# Connectors.net
KiCad netlist of a schematic drawn in Altium Designer
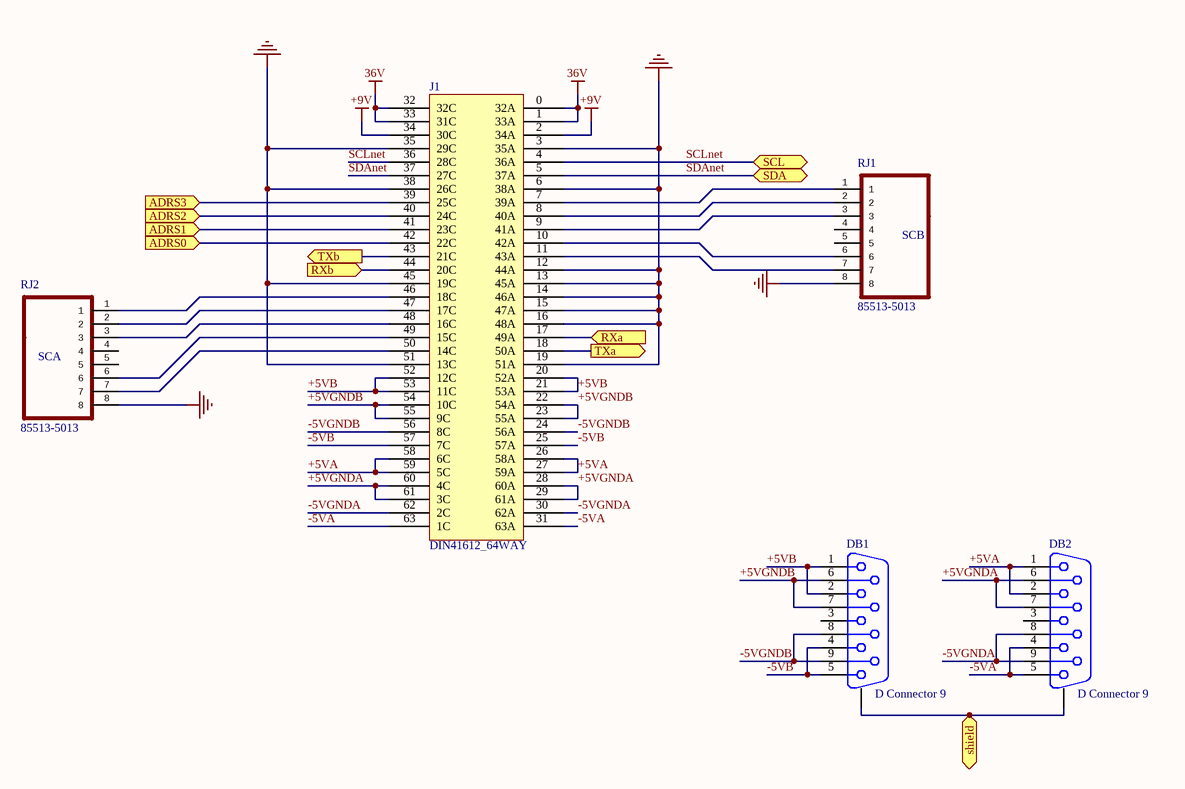
[diagram p0: Connectors.SchDoc]

(export (version "E")
  (design (tool "Eeschema 10.0.6"))
  (components
    (comp (ref "DB1")
      (value "D Connector 9")
      (footprint "DSUB1.STRAIGHT")
      (description "Receptacle Assembly, 9 Position, Right Angle")
      (fields (field (name "PARTNO") "L177TSEH09SOL2RM8") (field (name "PUBLISHER") "Altium Limited"))
      (libsource (lib "BACKPLANElib") (part "D Connector 9"))
    )
    (comp (ref "DB2")
      (value "D Connector 9")
      (footprint "DSUB1.STRAIGHT")
      (description "Receptacle Assembly, 9 Position, Right Angle")
      (fields (field (name "PARTNO") "L177TSEH09SOL2RM8") (field (name "PUBLISHER") "Altium Limited"))
      (libsource (lib "BACKPLANElib") (part "D Connector 9"))
    )
    (comp (ref "J1")
      (value "DIN41612_64WAY")
      (footprint "09 03 164 6919")
      (fields (field (name "PARTNO") "9-1393640-3"))
      (libsource (lib "BACKPLANElib") (part "DIN41612_64WAY"))
    )
    (comp (ref "RJ1")
      (value "85513-5013")
      (footprint "RJ45_SMD_VERT")
      (libsource (lib "BACKPLANElib") (part "85513-5013"))
    )
    (comp (ref "RJ2")
      (value "85513-5013")
      (footprint "RJ45_SMD_VERT")
      (libsource (lib "BACKPLANElib") (part "85513-5013"))
    )
  )
  (nets
    (net (code "1") (name "+9V") (class "Default")
      (node (ref "J1") (pin "2") (pinfunction "34A_2") (pintype "passive"))
      (node (ref "J1") (pin "34") (pinfunction "30C_34") (pintype "passive"))
    )
    (net (code "2") (name "/+5VA") (class "Default")
      (node (ref "DB2") (pin "1") (pinfunction "1_1") (pintype "passive"))
      (node (ref "DB2") (pin "2") (pinfunction "2_2") (pintype "passive"))
      (node (ref "J1") (pin "26") (pinfunction "58A_26") (pintype "passive"))
      (node (ref "J1") (pin "27") (pinfunction "59A_27") (pintype "passive"))
      (node (ref "J1") (pin "58") (pinfunction "6C_58") (pintype "passive"))
      (node (ref "J1") (pin "59") (pinfunction "5C_59") (pintype "passive"))
    )
    (net (code "3") (name "/+5VB") (class "Default")
      (node (ref "DB1") (pin "1") (pinfunction "1_1") (pintype "passive"))
      (node (ref "DB1") (pin "2") (pinfunction "2_2") (pintype "passive"))
      (node (ref "J1") (pin "20") (pinfunction "52A_20") (pintype "passive"))
      (node (ref "J1") (pin "21") (pinfunction "53A_21") (pintype "passive"))
      (node (ref "J1") (pin "52") (pinfunction "12C_52") (pintype "passive"))
      (node (ref "J1") (pin "53") (pinfunction "11C_53") (pintype "passive"))
    )
    (net (code "4") (name "/+5VGNDA") (class "Default")
      (node (ref "DB2") (pin "6") (pinfunction "6_6") (pintype "passive"))
      (node (ref "DB2") (pin "7") (pinfunction "7_7") (pintype "passive"))
      (node (ref "J1") (pin "28") (pinfunction "60A_28") (pintype "passive"))
      (node (ref "J1") (pin "29") (pinfunction "61A_29") (pintype "passive"))
      (node (ref "J1") (pin "60") (pinfunction "4C_60") (pintype "passive"))
      (node (ref "J1") (pin "61") (pinfunction "3C_61") (pintype "passive"))
    )
    (net (code "5") (name "/+5VGNDB") (class "Default")
      (node (ref "DB1") (pin "6") (pinfunction "6_6") (pintype "passive"))
      (node (ref "DB1") (pin "7") (pinfunction "7_7") (pintype "passive"))
      (node (ref "J1") (pin "22") (pinfunction "54A_22") (pintype "passive"))
      (node (ref "J1") (pin "23") (pinfunction "55A_23") (pintype "passive"))
      (node (ref "J1") (pin "54") (pinfunction "10C_54") (pintype "passive"))
      (node (ref "J1") (pin "55") (pinfunction "9C_55") (pintype "passive"))
    )
    (net (code "6") (name "/-5VA") (class "Default")
      (node (ref "DB2") (pin "4") (pinfunction "4_4") (pintype "passive"))
      (node (ref "DB2") (pin "5") (pinfunction "5_5") (pintype "passive"))
      (node (ref "J1") (pin "31") (pinfunction "63A_31") (pintype "passive"))
      (node (ref "J1") (pin "63") (pinfunction "1C_63") (pintype "passive"))
    )
    (net (code "7") (name "/-5VB") (class "Default")
      (node (ref "DB1") (pin "4") (pinfunction "4_4") (pintype "passive"))
      (node (ref "DB1") (pin "5") (pinfunction "5_5") (pintype "passive"))
      (node (ref "J1") (pin "25") (pinfunction "57A_25") (pintype "passive"))
      (node (ref "J1") (pin "57") (pinfunction "7C_57") (pintype "passive"))
    )
    (net (code "8") (name "/-5VGNDA") (class "Default")
      (node (ref "DB2") (pin "8") (pinfunction "8_8") (pintype "passive"))
      (node (ref "DB2") (pin "9") (pinfunction "9_9") (pintype "passive"))
      (node (ref "J1") (pin "30") (pinfunction "62A_30") (pintype "passive"))
      (node (ref "J1") (pin "62") (pinfunction "2C_62") (pintype "passive"))
    )
    (net (code "9") (name "/-5VGNDB") (class "Default")
      (node (ref "DB1") (pin "8") (pinfunction "8_8") (pintype "passive"))
      (node (ref "DB1") (pin "9") (pinfunction "9_9") (pintype "passive"))
      (node (ref "J1") (pin "24") (pinfunction "56A_24") (pintype "passive"))
      (node (ref "J1") (pin "56") (pinfunction "8C_56") (pintype "passive"))
    )
    (net (code "10") (name "/ADRS0") (class "Default")
      (node (ref "J1") (pin "42") (pinfunction "22C_42") (pintype "passive"))
    )
    (net (code "11") (name "/ADRS1") (class "Default")
      (node (ref "J1") (pin "41") (pinfunction "23C_41") (pintype "passive"))
    )
    (net (code "12") (name "/ADRS2") (class "Default")
      (node (ref "J1") (pin "40") (pinfunction "24C_40") (pintype "passive"))
    )
    (net (code "13") (name "/ADRS3") (class "Default")
      (node (ref "J1") (pin "39") (pinfunction "25C_39") (pintype "passive"))
    )
    (net (code "14") (name "/RXa") (class "Default")
      (node (ref "J1") (pin "17") (pinfunction "49A_17") (pintype "passive"))
    )
    (net (code "15") (name "/RXb") (class "Default")
      (node (ref "J1") (pin "44") (pinfunction "20C_44") (pintype "passive"))
    )
    (net (code "16") (name "/SCLnet") (class "Default")
      (node (ref "J1") (pin "36") (pinfunction "28C_36") (pintype "passive"))
      (node (ref "J1") (pin "4") (pinfunction "36A_4") (pintype "passive"))
    )
    (net (code "17") (name "/SDAnet") (class "Default")
      (node (ref "J1") (pin "37") (pinfunction "27C_37") (pintype "passive"))
      (node (ref "J1") (pin "5") (pinfunction "37A_5") (pintype "passive"))
    )
    (net (code "18") (name "/TXa") (class "Default")
      (node (ref "J1") (pin "18") (pinfunction "50A_18") (pintype "passive"))
    )
    (net (code "19") (name "/TXb") (class "Default")
      (node (ref "J1") (pin "43") (pinfunction "21C_43") (pintype "passive"))
    )
    (net (code "20") (name "/shield") (class "Default")
      (node (ref "DB1") (pin "0") (pinfunction "0_0") (pintype "passive"))
      (node (ref "DB2") (pin "0") (pinfunction "0_0") (pintype "passive"))
    )
    (net (code "21") (name "36V") (class "Default")
      (node (ref "J1") (pin "0") (pinfunction "32A_0") (pintype "passive"))
      (node (ref "J1") (pin "1") (pinfunction "33A_1") (pintype "passive"))
      (node (ref "J1") (pin "32") (pinfunction "32C_32") (pintype "passive"))
      (node (ref "J1") (pin "33") (pinfunction "31C_33") (pintype "passive"))
    )
    (net (code "22") (name "GND") (class "Default")
      (node (ref "J1") (pin "12") (pinfunction "44A_12") (pintype "passive"))
      (node (ref "J1") (pin "13") (pinfunction "45A_13") (pintype "passive"))
      (node (ref "J1") (pin "14") (pinfunction "46A_14") (pintype "passive"))
      (node (ref "J1") (pin "15") (pinfunction "47A_15") (pintype "passive"))
      (node (ref "J1") (pin "16") (pinfunction "48A_16") (pintype "passive"))
      (node (ref "J1") (pin "19") (pinfunction "51A_19") (pintype "passive"))
      (node (ref "J1") (pin "3") (pinfunction "35A_3") (pintype "passive"))
      (node (ref "J1") (pin "35") (pinfunction "29C_35") (pintype "passive"))
      (node (ref "J1") (pin "38") (pinfunction "26C_38") (pintype "passive"))
      (node (ref "J1") (pin "45") (pinfunction "19C_45") (pintype "passive"))
      (node (ref "J1") (pin "51") (pinfunction "13C_51") (pintype "passive"))
      (node (ref "J1") (pin "6") (pinfunction "38A_6") (pintype "passive"))
      (node (ref "RJ1") (pin "8") (pinfunction "8_8") (pintype "passive"))
      (node (ref "RJ2") (pin "8") (pinfunction "8_8") (pintype "passive"))
    )
    (net (code "23") (name "Net-(J1-14C)") (class "Default")
      (node (ref "J1") (pin "50") (pinfunction "14C_50") (pintype "passive"))
      (node (ref "RJ2") (pin "7") (pinfunction "7_7") (pintype "passive"))
    )
    (net (code "24") (name "Net-(J1-15C)") (class "Default")
      (node (ref "J1") (pin "49") (pinfunction "15C_49") (pintype "passive"))
      (node (ref "RJ2") (pin "6") (pinfunction "6_6") (pintype "passive"))
    )
    (net (code "25") (name "Net-(J1-16C)") (class "Default")
      (node (ref "J1") (pin "48") (pinfunction "16C_48") (pintype "passive"))
      (node (ref "RJ2") (pin "3") (pinfunction "3_3") (pintype "passive"))
    )
    (net (code "26") (name "Net-(J1-17C)") (class "Default")
      (node (ref "J1") (pin "47") (pinfunction "17C_47") (pintype "passive"))
      (node (ref "RJ2") (pin "2") (pinfunction "2_2") (pintype "passive"))
    )
    (net (code "27") (name "Net-(J1-18C)") (class "Default")
      (node (ref "J1") (pin "46") (pinfunction "18C_46") (pintype "passive"))
      (node (ref "RJ2") (pin "1") (pinfunction "1_1") (pintype "passive"))
    )
    (net (code "28") (name "Net-(J1-39A)") (class "Default")
      (node (ref "J1") (pin "7") (pinfunction "39A_7") (pintype "passive"))
      (node (ref "RJ1") (pin "1") (pinfunction "1_1") (pintype "passive"))
    )
    (net (code "29") (name "Net-(J1-40A)") (class "Default")
      (node (ref "J1") (pin "8") (pinfunction "40A_8") (pintype "passive"))
      (node (ref "RJ1") (pin "2") (pinfunction "2_2") (pintype "passive"))
    )
    (net (code "30") (name "Net-(J1-41A)") (class "Default")
      (node (ref "J1") (pin "9") (pinfunction "41A_9") (pintype "passive"))
      (node (ref "RJ1") (pin "3") (pinfunction "3_3") (pintype "passive"))
    )
    (net (code "31") (name "Net-(J1-42A)") (class "Default")
      (node (ref "J1") (pin "10") (pinfunction "42A_10") (pintype "passive"))
      (node (ref "RJ1") (pin "6") (pinfunction "6_6") (pintype "passive"))
    )
    (net (code "32") (name "Net-(J1-43A)") (class "Default")
      (node (ref "J1") (pin "11") (pinfunction "43A_11") (pintype "passive"))
      (node (ref "RJ1") (pin "7") (pinfunction "7_7") (pintype "passive"))
    )
    (net (code "33") (name "unconnected-(DB1-Pad3)") (class "Default")
      (node (ref "DB1") (pin "3") (pinfunction "3_3") (pintype "passive"))
    )
    (net (code "34") (name "unconnected-(DB2-Pad3)") (class "Default")
      (node (ref "DB2") (pin "3") (pinfunction "3_3") (pintype "passive"))
    )
    (net (code "35") (name "unconnected-(RJ1-Pad4)") (class "Default")
      (node (ref "RJ1") (pin "4") (pinfunction "4_4") (pintype "passive"))
    )
    (net (code "36") (name "unconnected-(RJ1-Pad5)") (class "Default")
      (node (ref "RJ1") (pin "5") (pinfunction "5_5") (pintype "passive"))
    )
    (net (code "37") (name "unconnected-(RJ2-Pad4)") (class "Default")
      (node (ref "RJ2") (pin "4") (pinfunction "4_4") (pintype "passive"))
    )
    (net (code "38") (name "unconnected-(RJ2-Pad5)") (class "Default")
      (node (ref "RJ2") (pin "5") (pinfunction "5_5") (pintype "passive"))
    )
  )
)
